# Load_Cape.net
KiCad netlist of a schematic drawn in EAGLE
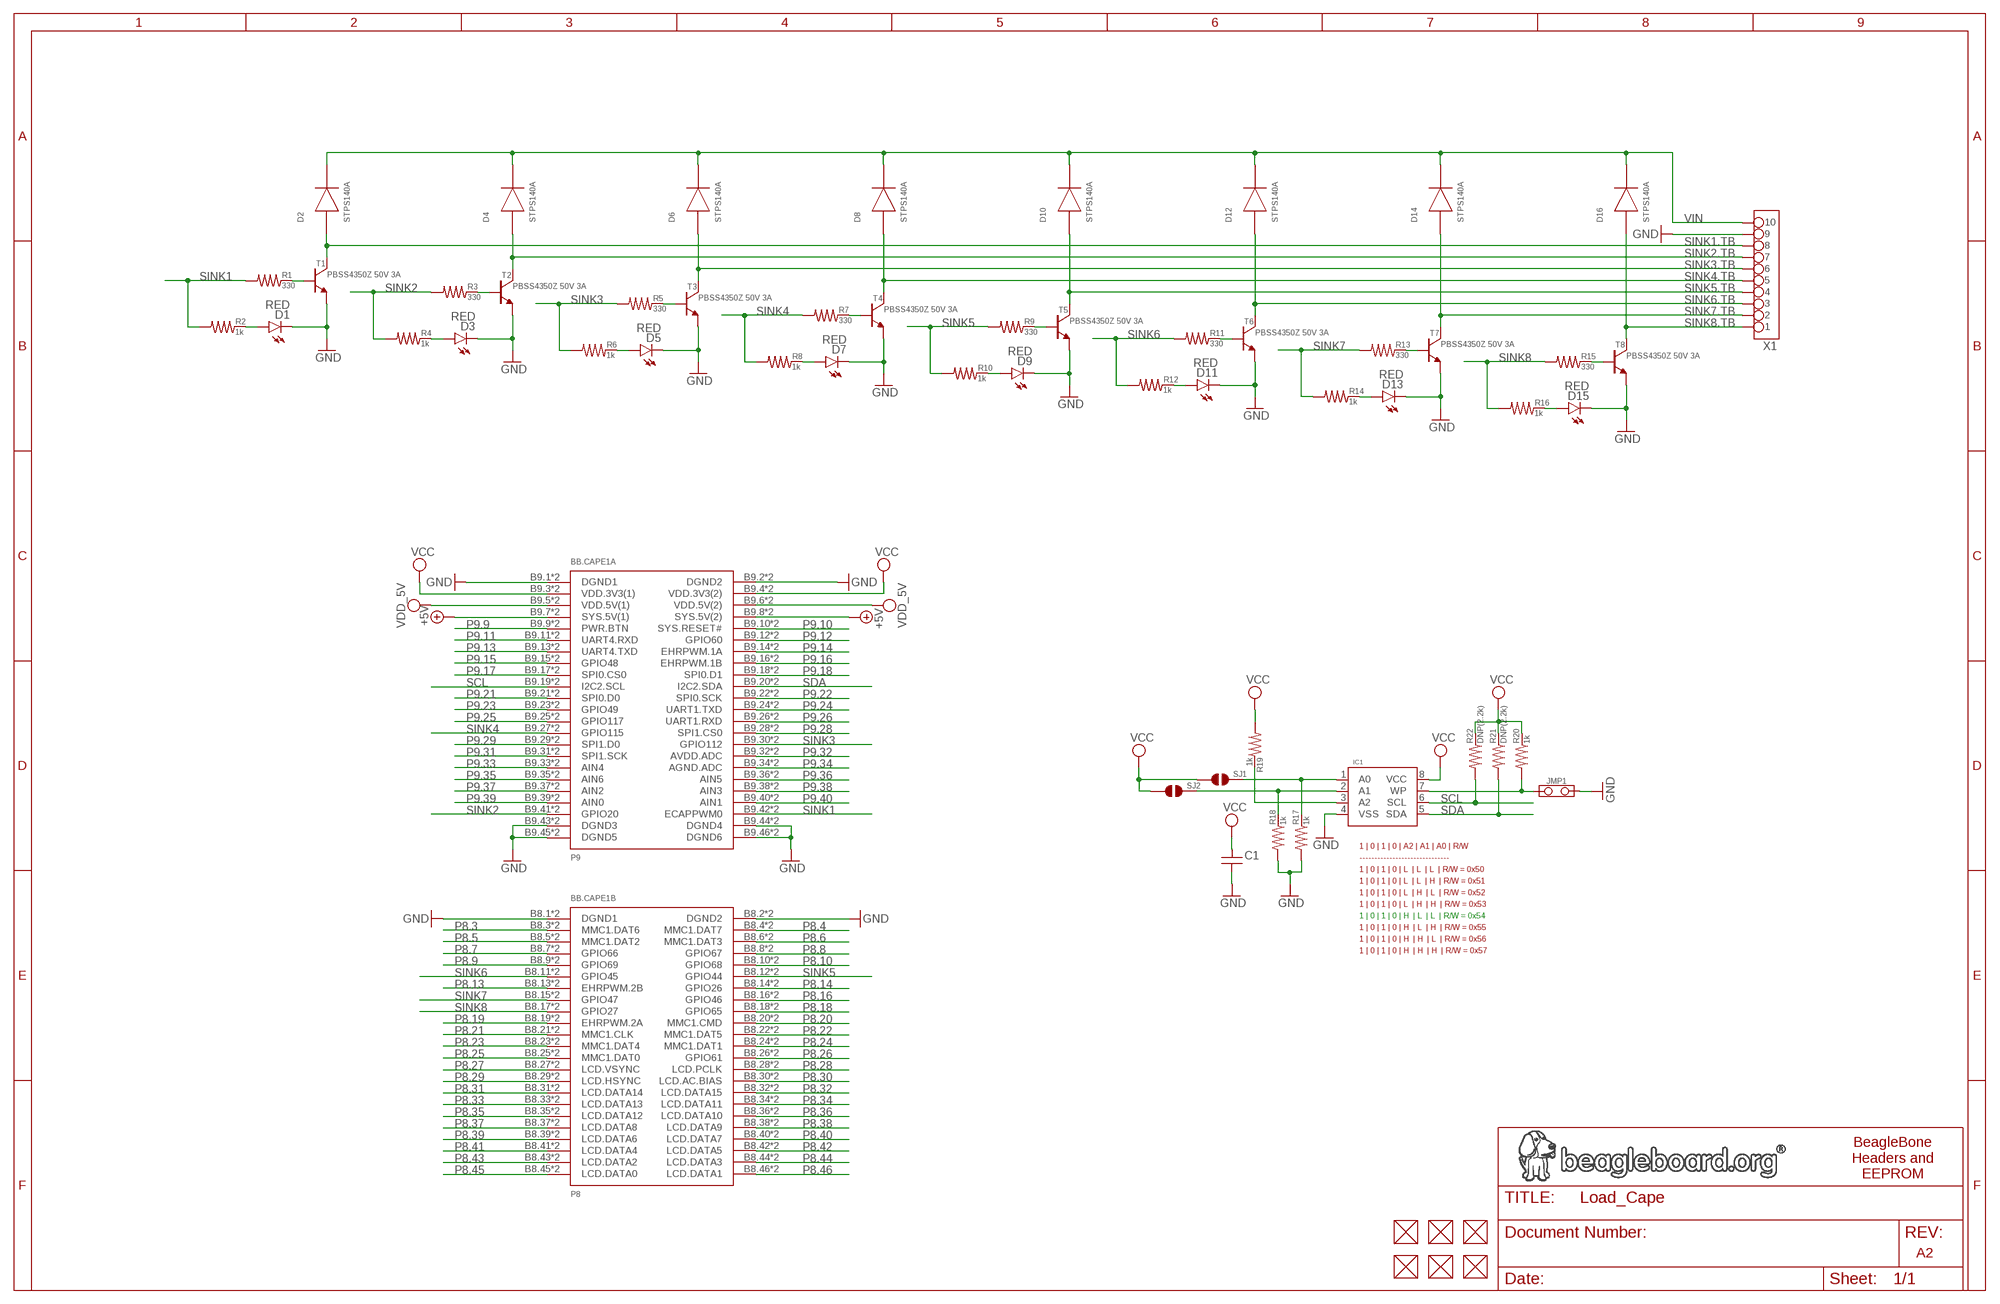
[diagram p0: schematic, sheet 1]

(export (version "E")
  (design (tool "Eeschema 10.0.6"))
  (components
    (comp (ref "BB.CAPE1")
      (value "BEAGLEBONE.CAPE.TOP/BOTTOM-PADS")
      (footprint "eagle-import:BEAGLEBONE.CAPE.TOP_BOTTOM-PADS")
      (libsource (lib "eagle-import") (part "BEAGLEBONE.CAPE.TOP/BOTTOM-PADS"))
    )
    (comp (ref "C1")
      (value "CAPACITOR-(INCH)-0402")
      (footprint "eagle-import:0402")
      (libsource (lib "eagle-import") (part "CAPACITOR-(INCH)-0402"))
    )
    (comp (ref "D1")
      (value "RED")
      (footprint "eagle-import:0805-LED")
      (libsource (lib "eagle-import") (part "LED-(INCH)-0805"))
    )
    (comp (ref "D2")
      (value "STPS140A")
      (footprint "eagle-import:DIODE_SMA")
      (libsource (lib "eagle-import") (part "DIODE_SMA"))
    )
    (comp (ref "D3")
      (value "RED")
      (footprint "eagle-import:0805-LED")
      (libsource (lib "eagle-import") (part "LED-(INCH)-0805"))
    )
    (comp (ref "D4")
      (value "STPS140A")
      (footprint "eagle-import:DIODE_SMA")
      (libsource (lib "eagle-import") (part "DIODE_SMA"))
    )
    (comp (ref "D5")
      (value "RED")
      (footprint "eagle-import:0805-LED")
      (libsource (lib "eagle-import") (part "LED-(INCH)-0805"))
    )
    (comp (ref "D6")
      (value "STPS140A")
      (footprint "eagle-import:DIODE_SMA")
      (libsource (lib "eagle-import") (part "DIODE_SMA"))
    )
    (comp (ref "D7")
      (value "RED")
      (footprint "eagle-import:0805-LED")
      (libsource (lib "eagle-import") (part "LED-(INCH)-0805"))
    )
    (comp (ref "D8")
      (value "STPS140A")
      (footprint "eagle-import:DIODE_SMA")
      (libsource (lib "eagle-import") (part "DIODE_SMA"))
    )
    (comp (ref "D9")
      (value "RED")
      (footprint "eagle-import:0805-LED")
      (libsource (lib "eagle-import") (part "LED-(INCH)-0805"))
    )
    (comp (ref "D10")
      (value "STPS140A")
      (footprint "eagle-import:DIODE_SMA")
      (libsource (lib "eagle-import") (part "DIODE_SMA"))
    )
    (comp (ref "D11")
      (value "RED")
      (footprint "eagle-import:0805-LED")
      (libsource (lib "eagle-import") (part "LED-(INCH)-0805"))
    )
    (comp (ref "D12")
      (value "STPS140A")
      (footprint "eagle-import:DIODE_SMA")
      (libsource (lib "eagle-import") (part "DIODE_SMA"))
    )
    (comp (ref "D13")
      (value "RED")
      (footprint "eagle-import:0805-LED")
      (libsource (lib "eagle-import") (part "LED-(INCH)-0805"))
    )
    (comp (ref "D14")
      (value "STPS140A")
      (footprint "eagle-import:DIODE_SMA")
      (libsource (lib "eagle-import") (part "DIODE_SMA"))
    )
    (comp (ref "D15")
      (value "RED")
      (footprint "eagle-import:0805-LED")
      (libsource (lib "eagle-import") (part "LED-(INCH)-0805"))
    )
    (comp (ref "D16")
      (value "STPS140A")
      (footprint "eagle-import:DIODE_SMA")
      (libsource (lib "eagle-import") (part "DIODE_SMA"))
    )
    (comp (ref "FUD1")
      (value "FIDUCIAL")
      (footprint "eagle-import:FIDUCIAL_40MIL")
      (libsource (lib "eagle-import") (part "FIDUCIAL"))
    )
    (comp (ref "FUD2")
      (value "FIDUCIAL")
      (footprint "eagle-import:FIDUCIAL_40MIL")
      (libsource (lib "eagle-import") (part "FIDUCIAL"))
    )
    (comp (ref "FUD3")
      (value "FIDUCIAL")
      (footprint "eagle-import:FIDUCIAL_40MIL")
      (libsource (lib "eagle-import") (part "FIDUCIAL"))
    )
    (comp (ref "FUD4")
      (value "FIDUCIAL")
      (footprint "eagle-import:FIDUCIAL_40MIL")
      (libsource (lib "eagle-import") (part "FIDUCIAL"))
    )
    (comp (ref "FUD5")
      (value "FIDUCIAL")
      (footprint "eagle-import:FIDUCIAL_40MIL")
      (libsource (lib "eagle-import") (part "FIDUCIAL"))
    )
    (comp (ref "FUD6")
      (value "FIDUCIAL")
      (footprint "eagle-import:FIDUCIAL_40MIL")
      (libsource (lib "eagle-import") (part "FIDUCIAL"))
    )
    (comp (ref "IC1")
      (value "CAT24C32")
      (footprint "eagle-import:UDFN8,2X3(ON-SEMI)")
      (libsource (lib "eagle-import") (part "CAT24C32"))
    )
    (comp (ref "JMP1")
      (value "JUMPER-(X2)")
      (footprint "eagle-import:JUMPER-(X2)")
      (libsource (lib "eagle-import") (part "JUMPER-(X2)"))
    )
    (comp (ref "R1")
      (value "330")
      (footprint "eagle-import:0402")
      (libsource (lib "eagle-import") (part "RESISTOR-(INCH)-0402"))
    )
    (comp (ref "R2")
      (value "1k")
      (footprint "eagle-import:0402")
      (libsource (lib "eagle-import") (part "RESISTOR-(INCH)-0402"))
    )
    (comp (ref "R3")
      (value "330")
      (footprint "eagle-import:0402")
      (libsource (lib "eagle-import") (part "RESISTOR-(INCH)-0402"))
    )
    (comp (ref "R4")
      (value "1k")
      (footprint "eagle-import:0402")
      (libsource (lib "eagle-import") (part "RESISTOR-(INCH)-0402"))
    )
    (comp (ref "R5")
      (value "330")
      (footprint "eagle-import:0402")
      (libsource (lib "eagle-import") (part "RESISTOR-(INCH)-0402"))
    )
    (comp (ref "R6")
      (value "1k")
      (footprint "eagle-import:0402")
      (libsource (lib "eagle-import") (part "RESISTOR-(INCH)-0402"))
    )
    (comp (ref "R7")
      (value "330")
      (footprint "eagle-import:0402")
      (libsource (lib "eagle-import") (part "RESISTOR-(INCH)-0402"))
    )
    (comp (ref "R8")
      (value "1k")
      (footprint "eagle-import:0402")
      (libsource (lib "eagle-import") (part "RESISTOR-(INCH)-0402"))
    )
    (comp (ref "R9")
      (value "330")
      (footprint "eagle-import:0402")
      (libsource (lib "eagle-import") (part "RESISTOR-(INCH)-0402"))
    )
    (comp (ref "R10")
      (value "1k")
      (footprint "eagle-import:0402")
      (libsource (lib "eagle-import") (part "RESISTOR-(INCH)-0402"))
    )
    (comp (ref "R11")
      (value "330")
      (footprint "eagle-import:0402")
      (libsource (lib "eagle-import") (part "RESISTOR-(INCH)-0402"))
    )
    (comp (ref "R12")
      (value "1k")
      (footprint "eagle-import:0402")
      (libsource (lib "eagle-import") (part "RESISTOR-(INCH)-0402"))
    )
    (comp (ref "R13")
      (value "330")
      (footprint "eagle-import:0402")
      (libsource (lib "eagle-import") (part "RESISTOR-(INCH)-0402"))
    )
    (comp (ref "R14")
      (value "1k")
      (footprint "eagle-import:0402")
      (libsource (lib "eagle-import") (part "RESISTOR-(INCH)-0402"))
    )
    (comp (ref "R15")
      (value "330")
      (footprint "eagle-import:0402")
      (libsource (lib "eagle-import") (part "RESISTOR-(INCH)-0402"))
    )
    (comp (ref "R16")
      (value "1k")
      (footprint "eagle-import:0402")
      (libsource (lib "eagle-import") (part "RESISTOR-(INCH)-0402"))
    )
    (comp (ref "R17")
      (value "1k")
      (footprint "eagle-import:0402")
      (libsource (lib "eagle-import") (part "RESISTOR-(INCH)-0402"))
    )
    (comp (ref "R18")
      (value "1k")
      (footprint "eagle-import:0402")
      (libsource (lib "eagle-import") (part "RESISTOR-(INCH)-0402"))
    )
    (comp (ref "R19")
      (value "1k")
      (footprint "eagle-import:0402")
      (libsource (lib "eagle-import") (part "RESISTOR-(INCH)-0402"))
    )
    (comp (ref "R20")
      (value "1k")
      (footprint "eagle-import:0402")
      (libsource (lib "eagle-import") (part "RESISTOR-(INCH)-0402"))
    )
    (comp (ref "R21")
      (value "DNP(2.2k)")
      (footprint "eagle-import:0402")
      (libsource (lib "eagle-import") (part "RESISTOR-(INCH)-0402"))
    )
    (comp (ref "R22")
      (value "DNP(2.2k)")
      (footprint "eagle-import:0402")
      (libsource (lib "eagle-import") (part "RESISTOR-(INCH)-0402"))
    )
    (comp (ref "SJ1")
      (value "SOLDER.JOINT-(INCH)-0402")
      (footprint "eagle-import:SOLDER.JOINT(0402)")
      (libsource (lib "eagle-import") (part "SOLDER.JOINT-(INCH)-0402"))
    )
    (comp (ref "SJ2")
      (value "SOLDER.JOINT-(INCH)-0402")
      (footprint "eagle-import:SOLDER.JOINT(0402)")
      (libsource (lib "eagle-import") (part "SOLDER.JOINT-(INCH)-0402"))
    )
    (comp (ref "T1")
      (value "PBSS4350Z 50V 3A")
      (footprint "eagle-import:SOT223")
      (libsource (lib "eagle-import") (part "PBSS4350Z"))
    )
    (comp (ref "T2")
      (value "PBSS4350Z 50V 3A")
      (footprint "eagle-import:SOT223")
      (libsource (lib "eagle-import") (part "PBSS4350Z"))
    )
    (comp (ref "T3")
      (value "PBSS4350Z 50V 3A")
      (footprint "eagle-import:SOT223")
      (libsource (lib "eagle-import") (part "PBSS4350Z"))
    )
    (comp (ref "T4")
      (value "PBSS4350Z 50V 3A")
      (footprint "eagle-import:SOT223")
      (libsource (lib "eagle-import") (part "PBSS4350Z"))
    )
    (comp (ref "T5")
      (value "PBSS4350Z 50V 3A")
      (footprint "eagle-import:SOT223")
      (libsource (lib "eagle-import") (part "PBSS4350Z"))
    )
    (comp (ref "T6")
      (value "PBSS4350Z 50V 3A")
      (footprint "eagle-import:SOT223")
      (libsource (lib "eagle-import") (part "PBSS4350Z"))
    )
    (comp (ref "T7")
      (value "PBSS4350Z 50V 3A")
      (footprint "eagle-import:SOT223")
      (libsource (lib "eagle-import") (part "PBSS4350Z"))
    )
    (comp (ref "T8")
      (value "PBSS4350Z 50V 3A")
      (footprint "eagle-import:SOT223")
      (libsource (lib "eagle-import") (part "PBSS4350Z"))
    )
    (comp (ref "X1")
      (value "TB-10TERM-150MIL.PITCH")
      (footprint "eagle-import:TERMINAL.BLOCK-10TERM-150MIL.PITCH")
      (libsource (lib "eagle-import") (part "TB-10TERM-150MIL.PITCH"))
    )
  )
  (nets
    (net (code "1") (name "+5V") (class "Default")
      (node (ref "BB.CAPE1") (pin "B9.7") (pinfunction "SYS.5V(1)_B9.7") (pintype "bidirectional"))
      (node (ref "BB.CAPE1") (pin "B9.8") (pinfunction "SYS.5V(2)_B9.8") (pintype "bidirectional"))
      (node (ref "BB.CAPE1") (pin "T9.7") (pinfunction "SYS.5V(1)_T9.7") (pintype "bidirectional"))
      (node (ref "BB.CAPE1") (pin "T9.8") (pinfunction "SYS.5V(2)_T9.8") (pintype "bidirectional"))
    )
    (net (code "2") (name "/P8.3") (class "Default")
      (node (ref "BB.CAPE1") (pin "B8.3") (pinfunction "MMC1.DAT6_B8.3") (pintype "bidirectional"))
      (node (ref "BB.CAPE1") (pin "T8.3") (pinfunction "MMC1.DAT6_T8.3") (pintype "bidirectional"))
    )
    (net (code "3") (name "/P8.4") (class "Default")
      (node (ref "BB.CAPE1") (pin "B8.4") (pinfunction "MMC1.DAT7_B8.4") (pintype "bidirectional"))
      (node (ref "BB.CAPE1") (pin "T8.4") (pinfunction "MMC1.DAT7_T8.4") (pintype "bidirectional"))
    )
    (net (code "4") (name "/P8.5") (class "Default")
      (node (ref "BB.CAPE1") (pin "B8.5") (pinfunction "MMC1.DAT2_B8.5") (pintype "bidirectional"))
      (node (ref "BB.CAPE1") (pin "T8.5") (pinfunction "MMC1.DAT2_T8.5") (pintype "bidirectional"))
    )
    (net (code "5") (name "/P8.6") (class "Default")
      (node (ref "BB.CAPE1") (pin "B8.6") (pinfunction "MMC1.DAT3_B8.6") (pintype "bidirectional"))
      (node (ref "BB.CAPE1") (pin "T8.6") (pinfunction "MMC1.DAT3_T8.6") (pintype "bidirectional"))
    )
    (net (code "6") (name "/P8.7") (class "Default")
      (node (ref "BB.CAPE1") (pin "B8.7") (pinfunction "GPIO66_B8.7") (pintype "bidirectional"))
      (node (ref "BB.CAPE1") (pin "T8.7") (pinfunction "GPIO66_T8.7") (pintype "bidirectional"))
    )
    (net (code "7") (name "/P8.8") (class "Default")
      (node (ref "BB.CAPE1") (pin "B8.8") (pinfunction "GPIO67_B8.8") (pintype "bidirectional"))
      (node (ref "BB.CAPE1") (pin "T8.8") (pinfunction "GPIO67_T8.8") (pintype "bidirectional"))
    )
    (net (code "8") (name "/P8.9") (class "Default")
      (node (ref "BB.CAPE1") (pin "B8.9") (pinfunction "GPIO69_B8.9") (pintype "bidirectional"))
      (node (ref "BB.CAPE1") (pin "T8.9") (pinfunction "GPIO69_T8.9") (pintype "bidirectional"))
    )
    (net (code "9") (name "/P8.10") (class "Default")
      (node (ref "BB.CAPE1") (pin "B8.10") (pinfunction "GPIO68_B8.10") (pintype "bidirectional"))
      (node (ref "BB.CAPE1") (pin "T8.10") (pinfunction "GPIO68_T8.10") (pintype "bidirectional"))
    )
    (net (code "10") (name "/P8.13") (class "Default")
      (node (ref "BB.CAPE1") (pin "B8.13") (pinfunction "EHRPWM.2B_B8.13") (pintype "bidirectional"))
      (node (ref "BB.CAPE1") (pin "T8.13") (pinfunction "EHRPWM.2B_T8.13") (pintype "bidirectional"))
    )
    (net (code "11") (name "/P8.14") (class "Default")
      (node (ref "BB.CAPE1") (pin "B8.14") (pinfunction "GPIO26_B8.14") (pintype "bidirectional"))
      (node (ref "BB.CAPE1") (pin "T8.14") (pinfunction "GPIO26_T8.14") (pintype "bidirectional"))
    )
    (net (code "12") (name "/P8.16") (class "Default")
      (node (ref "BB.CAPE1") (pin "B8.16") (pinfunction "GPIO46_B8.16") (pintype "bidirectional"))
      (node (ref "BB.CAPE1") (pin "T8.16") (pinfunction "GPIO46_T8.16") (pintype "bidirectional"))
    )
    (net (code "13") (name "/P8.18") (class "Default")
      (node (ref "BB.CAPE1") (pin "B8.18") (pinfunction "GPIO65_B8.18") (pintype "bidirectional"))
      (node (ref "BB.CAPE1") (pin "T8.18") (pinfunction "GPIO65_T8.18") (pintype "bidirectional"))
    )
    (net (code "14") (name "/P8.19") (class "Default")
      (node (ref "BB.CAPE1") (pin "B8.19") (pinfunction "EHRPWM.2A_B8.19") (pintype "bidirectional"))
      (node (ref "BB.CAPE1") (pin "T8.19") (pinfunction "EHRPWM.2A_T8.19") (pintype "bidirectional"))
    )
    (net (code "15") (name "/P8.20") (class "Default")
      (node (ref "BB.CAPE1") (pin "B8.20") (pinfunction "MMC1.CMD_B8.20") (pintype "bidirectional"))
      (node (ref "BB.CAPE1") (pin "T8.20") (pinfunction "MMC1.CMD_T8.20") (pintype "bidirectional"))
    )
    (net (code "16") (name "/P8.21") (class "Default")
      (node (ref "BB.CAPE1") (pin "B8.21") (pinfunction "MMC1.CLK_B8.21") (pintype "bidirectional"))
      (node (ref "BB.CAPE1") (pin "T8.21") (pinfunction "MMC1.CLK_T8.21") (pintype "bidirectional"))
    )
    (net (code "17") (name "/P8.22") (class "Default")
      (node (ref "BB.CAPE1") (pin "B8.22") (pinfunction "MMC1.DAT5_B8.22") (pintype "bidirectional"))
      (node (ref "BB.CAPE1") (pin "T8.22") (pinfunction "MMC1.DAT5_T8.22") (pintype "bidirectional"))
    )
    (net (code "18") (name "/P8.23") (class "Default")
      (node (ref "BB.CAPE1") (pin "B8.23") (pinfunction "MMC1.DAT4_B8.23") (pintype "bidirectional"))
      (node (ref "BB.CAPE1") (pin "T8.23") (pinfunction "MMC1.DAT4_T8.23") (pintype "bidirectional"))
    )
    (net (code "19") (name "/P8.24") (class "Default")
      (node (ref "BB.CAPE1") (pin "B8.24") (pinfunction "MMC1.DAT1_B8.24") (pintype "bidirectional"))
      (node (ref "BB.CAPE1") (pin "T8.24") (pinfunction "MMC1.DAT1_T8.24") (pintype "bidirectional"))
    )
    (net (code "20") (name "/P8.25") (class "Default")
      (node (ref "BB.CAPE1") (pin "B8.25") (pinfunction "MMC1.DAT0_B8.25") (pintype "bidirectional"))
      (node (ref "BB.CAPE1") (pin "T8.25") (pinfunction "MMC1.DAT0_T8.25") (pintype "bidirectional"))
    )
    (net (code "21") (name "/P8.26") (class "Default")
      (node (ref "BB.CAPE1") (pin "B8.26") (pinfunction "GPIO61_B8.26") (pintype "bidirectional"))
      (node (ref "BB.CAPE1") (pin "T8.26") (pinfunction "GPIO61_T8.26") (pintype "bidirectional"))
    )
    (net (code "22") (name "/P8.27") (class "Default")
      (node (ref "BB.CAPE1") (pin "B8.27") (pinfunction "LCD.VSYNC_B8.27") (pintype "bidirectional"))
      (node (ref "BB.CAPE1") (pin "T8.27") (pinfunction "LCD.VSYNC_T8.27") (pintype "bidirectional"))
    )
    (net (code "23") (name "/P8.28") (class "Default")
      (node (ref "BB.CAPE1") (pin "B8.28") (pinfunction "LCD.PCLK_B8.28") (pintype "bidirectional"))
      (node (ref "BB.CAPE1") (pin "T8.28") (pinfunction "LCD.PCLK_T8.28") (pintype "bidirectional"))
    )
    (net (code "24") (name "/P8.29") (class "Default")
      (node (ref "BB.CAPE1") (pin "B8.29") (pinfunction "LCD.HSYNC_B8.29") (pintype "bidirectional"))
      (node (ref "BB.CAPE1") (pin "T8.29") (pinfunction "LCD.HSYNC_T8.29") (pintype "bidirectional"))
    )
    (net (code "25") (name "/P8.30") (class "Default")
      (node (ref "BB.CAPE1") (pin "B8.30") (pinfunction "LCD.AC.BIAS_B8.30") (pintype "bidirectional"))
      (node (ref "BB.CAPE1") (pin "T8.30") (pinfunction "LCD.AC.BIAS_T8.30") (pintype "bidirectional"))
    )
    (net (code "26") (name "/P8.31") (class "Default")
      (node (ref "BB.CAPE1") (pin "B8.31") (pinfunction "LCD.DATA14_B8.31") (pintype "bidirectional"))
      (node (ref "BB.CAPE1") (pin "T8.31") (pinfunction "LCD.DATA14_T8.31") (pintype "bidirectional"))
    )
    (net (code "27") (name "/P8.32") (class "Default")
      (node (ref "BB.CAPE1") (pin "B8.32") (pinfunction "LCD.DATA15_B8.32") (pintype "bidirectional"))
      (node (ref "BB.CAPE1") (pin "T8.32") (pinfunction "LCD.DATA15_T8.32") (pintype "bidirectional"))
    )
    (net (code "28") (name "/P8.33") (class "Default")
      (node (ref "BB.CAPE1") (pin "B8.33") (pinfunction "LCD.DATA13_B8.33") (pintype "bidirectional"))
      (node (ref "BB.CAPE1") (pin "T8.33") (pinfunction "LCD.DATA13_T8.33") (pintype "bidirectional"))
    )
    (net (code "29") (name "/P8.34") (class "Default")
      (node (ref "BB.CAPE1") (pin "B8.34") (pinfunction "LCD.DATA11_B8.34") (pintype "bidirectional"))
      (node (ref "BB.CAPE1") (pin "T8.34") (pinfunction "LCD.DATA11_T8.34") (pintype "bidirectional"))
    )
    (net (code "30") (name "/P8.35") (class "Default")
      (node (ref "BB.CAPE1") (pin "B8.35") (pinfunction "LCD.DATA12_B8.35") (pintype "bidirectional"))
      (node (ref "BB.CAPE1") (pin "T8.35") (pinfunction "LCD.DATA12_T8.35") (pintype "bidirectional"))
    )
    (net (code "31") (name "/P8.36") (class "Default")
      (node (ref "BB.CAPE1") (pin "B8.36") (pinfunction "LCD.DATA10_B8.36") (pintype "bidirectional"))
      (node (ref "BB.CAPE1") (pin "T8.36") (pinfunction "LCD.DATA10_T8.36") (pintype "bidirectional"))
    )
    (net (code "32") (name "/P8.37") (class "Default")
      (node (ref "BB.CAPE1") (pin "B8.37") (pinfunction "LCD.DATA8_B8.37") (pintype "bidirectional"))
      (node (ref "BB.CAPE1") (pin "T8.37") (pinfunction "LCD.DATA8_T8.37") (pintype "bidirectional"))
    )
    (net (code "33") (name "/P8.38") (class "Default")
      (node (ref "BB.CAPE1") (pin "B8.38") (pinfunction "LCD.DATA9_B8.38") (pintype "bidirectional"))
      (node (ref "BB.CAPE1") (pin "T8.38") (pinfunction "LCD.DATA9_T8.38") (pintype "bidirectional"))
    )
    (net (code "34") (name "/P8.39") (class "Default")
      (node (ref "BB.CAPE1") (pin "B8.39") (pinfunction "LCD.DATA6_B8.39") (pintype "bidirectional"))
      (node (ref "BB.CAPE1") (pin "T8.39") (pinfunction "LCD.DATA6_T8.39") (pintype "bidirectional"))
    )
    (net (code "35") (name "/P8.40") (class "Default")
      (node (ref "BB.CAPE1") (pin "B8.40") (pinfunction "LCD.DATA7_B8.40") (pintype "bidirectional"))
      (node (ref "BB.CAPE1") (pin "T8.40") (pinfunction "LCD.DATA7_T8.40") (pintype "bidirectional"))
    )
    (net (code "36") (name "/P8.41") (class "Default")
      (node (ref "BB.CAPE1") (pin "B8.41") (pinfunction "LCD.DATA4_B8.41") (pintype "bidirectional"))
      (node (ref "BB.CAPE1") (pin "T8.41") (pinfunction "LCD.DATA4_T8.41") (pintype "bidirectional"))
    )
    (net (code "37") (name "/P8.42") (class "Default")
      (node (ref "BB.CAPE1") (pin "B8.42") (pinfunction "LCD.DATA5_B8.42") (pintype "bidirectional"))
      (node (ref "BB.CAPE1") (pin "T8.42") (pinfunction "LCD.DATA5_T8.42") (pintype "bidirectional"))
    )
    (net (code "38") (name "/P8.43") (class "Default")
      (node (ref "BB.CAPE1") (pin "B8.43") (pinfunction "LCD.DATA2_B8.43") (pintype "bidirectional"))
      (node (ref "BB.CAPE1") (pin "T8.43") (pinfunction "LCD.DATA2_T8.43") (pintype "bidirectional"))
    )
    (net (code "39") (name "/P8.44") (class "Default")
      (node (ref "BB.CAPE1") (pin "B8.44") (pinfunction "LCD.DATA3_B8.44") (pintype "bidirectional"))
      (node (ref "BB.CAPE1") (pin "T8.44") (pinfunction "LCD.DATA3_T8.44") (pintype "bidirectional"))
    )
    (net (code "40") (name "/P8.45") (class "Default")
      (node (ref "BB.CAPE1") (pin "B8.45") (pinfunction "LCD.DATA0_B8.45") (pintype "bidirectional"))
      (node (ref "BB.CAPE1") (pin "T8.45") (pinfunction "LCD.DATA0_T8.45") (pintype "bidirectional"))
    )
    (net (code "41") (name "/P8.46") (class "Default")
      (node (ref "BB.CAPE1") (pin "B8.46") (pinfunction "LCD.DATA1_B8.46") (pintype "bidirectional"))
      (node (ref "BB.CAPE1") (pin "T8.46") (pinfunction "LCD.DATA1_T8.46") (pintype "bidirectional"))
    )
    (net (code "42") (name "/P9.9") (class "Default")
      (node (ref "BB.CAPE1") (pin "B9.9") (pinfunction "PWR.BTN_B9.9") (pintype "bidirectional"))
      (node (ref "BB.CAPE1") (pin "T9.9") (pinfunction "PWR.BTN_T9.9") (pintype "bidirectional"))
    )
    (net (code "43") (name "/P9.10") (class "Default")
      (node (ref "BB.CAPE1") (pin "B9.10") (pinfunction "SYS.RESET#_B9.10") (pintype "bidirectional"))
      (node (ref "BB.CAPE1") (pin "T9.10") (pinfunction "SYS.RESET#_T9.10") (pintype "bidirectional"))
    )
    (net (code "44") (name "/P9.11") (class "Default")
      (node (ref "BB.CAPE1") (pin "B9.11") (pinfunction "UART4.RXD_B9.11") (pintype "bidirectional"))
      (node (ref "BB.CAPE1") (pin "T9.11") (pinfunction "UART4.RXD_T9.11") (pintype "bidirectional"))
    )
    (net (code "45") (name "/P9.12") (class "Default")
      (node (ref "BB.CAPE1") (pin "B9.12") (pinfunction "GPIO60_B9.12") (pintype "bidirectional"))
      (node (ref "BB.CAPE1") (pin "T9.12") (pinfunction "GPIO60_T9.12") (pintype "bidirectional"))
    )
    (net (code "46") (name "/P9.13") (class "Default")
      (node (ref "BB.CAPE1") (pin "B9.13") (pinfunction "UART4.TXD_B9.13") (pintype "bidirectional"))
      (node (ref "BB.CAPE1") (pin "T9.13") (pinfunction "UART4.TXD_T9.13") (pintype "bidirectional"))
    )
    (net (code "47") (name "/P9.14") (class "Default")
      (node (ref "BB.CAPE1") (pin "B9.14") (pinfunction "EHRPWM.1A_B9.14") (pintype "bidirectional"))
      (node (ref "BB.CAPE1") (pin "T9.14") (pinfunction "EHRPWM.1A_T9.14") (pintype "bidirectional"))
    )
    (net (code "48") (name "/P9.15") (class "Default")
      (node (ref "BB.CAPE1") (pin "B9.15") (pinfunction "GPIO48_B9.15") (pintype "bidirectional"))
      (node (ref "BB.CAPE1") (pin "T9.15") (pinfunction "GPIO48_T9.15") (pintype "bidirectional"))
    )
    (net (code "49") (name "/P9.16") (class "Default")
      (node (ref "BB.CAPE1") (pin "B9.16") (pinfunction "EHRPWM.1B_B9.16") (pintype "bidirectional"))
      (node (ref "BB.CAPE1") (pin "T9.16") (pinfunction "EHRPWM.1B_T9.16") (pintype "bidirectional"))
    )
    (net (code "50") (name "/P9.17") (class "Default")
      (node (ref "BB.CAPE1") (pin "B9.17") (pinfunction "SPI0.CS0_B9.17") (pintype "bidirectional"))
      (node (ref "BB.CAPE1") (pin "T9.17") (pinfunction "SPI0.CS0_T9.17") (pintype "bidirectional"))
    )
    (net (code "51") (name "/P9.18") (class "Default")
      (node (ref "BB.CAPE1") (pin "B9.18") (pinfunction "SPI0.D1_B9.18") (pintype "bidirectional"))
      (node (ref "BB.CAPE1") (pin "T9.18") (pinfunction "SPI0.D1_T9.18") (pintype "bidirectional"))
    )
    (net (code "52") (name "/P9.21") (class "Default")
      (node (ref "BB.CAPE1") (pin "B9.21") (pinfunction "SPI0.D0_B9.21") (pintype "bidirectional"))
      (node (ref "BB.CAPE1") (pin "T9.21") (pinfunction "SPI0.D0_T9.21") (pintype "bidirectional"))
    )
    (net (code "53") (name "/P9.22") (class "Default")
      (node (ref "BB.CAPE1") (pin "B9.22") (pinfunction "SPI0.SCK_B9.22") (pintype "bidirectional"))
      (node (ref "BB.CAPE1") (pin "T9.22") (pinfunction "SPI0.SCK_T9.22") (pintype "bidirectional"))
    )
    (net (code "54") (name "/P9.23") (class "Default")
      (node (ref "BB.CAPE1") (pin "B9.23") (pinfunction "GPIO49_B9.23") (pintype "bidirectional"))
      (node (ref "BB.CAPE1") (pin "T9.23") (pinfunction "GPIO49_T9.23") (pintype "bidirectional"))
    )
    (net (code "55") (name "/P9.24") (class "Default")
      (node (ref "BB.CAPE1") (pin "B9.24") (pinfunction "UART1.TXD_B9.24") (pintype "bidirectional"))
      (node (ref "BB.CAPE1") (pin "T9.24") (pinfunction "UART1.TXD_T9.24") (pintype "bidirectional"))
    )
    (net (code "56") (name "/P9.25") (class "Default")
      (node (ref "BB.CAPE1") (pin "B9.25") (pinfunction "GPIO117_B9.25") (pintype "bidirectional"))
      (node (ref "BB.CAPE1") (pin "T9.25") (pinfunction "GPIO117_T9.25") (pintype "bidirectional"))
    )
    (net (code "57") (name "/P9.26") (class "Default")
      (node (ref "BB.CAPE1") (pin "B9.26") (pinfunction "UART1.RXD_B9.26") (pintype "bidirectional"))
      (node (ref "BB.CAPE1") (pin "T9.26") (pinfunction "UART1.RXD_T9.26") (pintype "bidirectional"))
    )
    (net (code "58") (name "/P9.28") (class "Default")
      (node (ref "BB.CAPE1") (pin "B9.28") (pinfunction "SPI1.CS0_B9.28") (pintype "bidirectional"))
      (node (ref "BB.CAPE1") (pin "T9.28") (pinfunction "SPI1.CS0_T9.28") (pintype "bidirectional"))
    )
    (net (code "59") (name "/P9.29") (class "Default")
      (node (ref "BB.CAPE1") (pin "B9.29") (pinfunction "SPI1.D0_B9.29") (pintype "bidirectional"))
      (node (ref "BB.CAPE1") (pin "T9.29") (pinfunction "SPI1.D0_T9.29") (pintype "bidirectional"))
    )
    (net (code "60") (name "/P9.31") (class "Default")
      (node (ref "BB.CAPE1") (pin "B9.31") (pinfunction "SPI1.SCK_B9.31") (pintype "bidirectional"))
      (node (ref "BB.CAPE1") (pin "T9.31") (pinfunction "SPI1.SCK_T9.31") (pintype "bidirectional"))
    )
    (net (code "61") (name "/P9.32") (class "Default")
      (node (ref "BB.CAPE1") (pin "B9.32") (pinfunction "AVDD.ADC_B9.32") (pintype "bidirectional"))
      (node (ref "BB.CAPE1") (pin "T9.32") (pinfunction "AVDD.ADC_T9.32") (pintype "bidirectional"))
    )
    (net (code "62") (name "/P9.33") (class "Default")
      (node (ref "BB.CAPE1") (pin "B9.33") (pinfunction "AIN4_B9.33") (pintype "bidirectional"))
      (node (ref "BB.CAPE1") (pin "T9.33") (pinfunction "AIN4_T9.33") (pintype "bidirectional"))
    )
    (net (code "63") (name "/P9.34") (class "Default")
      (node (ref "BB.CAPE1") (pin "B9.34") (pinfunction "AGND.ADC_B9.34") (pintype "bidirectional"))
      (node (ref "BB.CAPE1") (pin "T9.34") (pinfunction "AGND.ADC_T9.34") (pintype "bidirectional"))
    )
    (net (code "64") (name "/P9.35") (class "Default")
      (node (ref "BB.CAPE1") (pin "B9.35") (pinfunction "AIN6_B9.35") (pintype "bidirectional"))
      (node (ref "BB.CAPE1") (pin "T9.35") (pinfunction "AIN6_T9.35") (pintype "bidirectional"))
    )
    (net (code "65") (name "/P9.36") (class "Default")
      (node (ref "BB.CAPE1") (pin "B9.36") (pinfunction "AIN5_B9.36") (pintype "bidirectional"))
      (node (ref "BB.CAPE1") (pin "T9.36") (pinfunction "AIN5_T9.36") (pintype "bidirectional"))
    )
    (net (code "66") (name "/P9.37") (class "Default")
      (node (ref "BB.CAPE1") (pin "B9.37") (pinfunction "AIN2_B9.37") (pintype "bidirectional"))
      (node (ref "BB.CAPE1") (pin "T9.37") (pinfunction "AIN2_T9.37") (pintype "bidirectional"))
    )
    (net (code "67") (name "/P9.38") (class "Default")
      (node (ref "BB.CAPE1") (pin "B9.38") (pinfunction "AIN3_B9.38") (pintype "bidirectional"))
      (node (ref "BB.CAPE1") (pin "T9.38") (pinfunction "AIN3_T9.38") (pintype "bidirectional"))
    )
    (net (code "68") (name "/P9.39") (class "Default")
      (node (ref "BB.CAPE1") (pin "B9.39") (pinfunction "AIN0_B9.39") (pintype "bidirectional"))
      (node (ref "BB.CAPE1") (pin "T9.39") (pinfunction "AIN0_T9.39") (pintype "bidirectional"))
    )
    (net (code "69") (name "/P9.40") (class "Default")
      (node (ref "BB.CAPE1") (pin "B9.40") (pinfunction "AIN1_B9.40") (pintype "bidirectional"))
      (node (ref "BB.CAPE1") (pin "T9.40") (pinfunction "AIN1_T9.40") (pintype "bidirectional"))
    )
    (net (code "70") (name "/SCL") (class "Default")
      (node (ref "BB.CAPE1") (pin "B9.19") (pinfunction "I2C2.SCL_B9.19") (pintype "bidirectional"))
      (node (ref "BB.CAPE1") (pin "T9.19") (pinfunction "I2C2.SCL_T9.19") (pintype "bidirectional"))
      (node (ref "IC1") (pin "6") (pinfunction "SCL_6") (pintype "bidirectional"))
      (node (ref "R22") (pin "1") (pinfunction "1_1") (pintype "bidirectional"))
    )
    (net (code "71") (name "/SDA") (class "Default")
      (node (ref "BB.CAPE1") (pin "B9.20") (pinfunction "I2C2.SDA_B9.20") (pintype "bidirectional"))
      (node (ref "BB.CAPE1") (pin "T9.20") (pinfunction "I2C2.SDA_T9.20") (pintype "bidirectional"))
      (node (ref "IC1") (pin "5") (pinfunction "SDA_5") (pintype "bidirectional"))
      (node (ref "R21") (pin "1") (pinfunction "1_1") (pintype "bidirectional"))
    )
    (net (code "72") (name "/SINK1") (class "Default")
      (node (ref "BB.CAPE1") (pin "B9.42") (pinfunction "ECAPPWM0_B9.42") (pintype "bidirectional"))
      (node (ref "BB.CAPE1") (pin "T9.42") (pinfunction "ECAPPWM0_T9.42") (pintype "bidirectional"))
      (node (ref "R1") (pin "1") (pinfunction "1_1") (pintype "bidirectional"))
      (node (ref "R2") (pin "1") (pinfunction "1_1") (pintype "bidirectional"))
    )
    (net (code "73") (name "/SINK1.TB") (class "Default")
      (node (ref "D2") (pin "A") (pinfunction "A_A") (pintype "bidirectional"))
      (node (ref "T1") (pin "2") (pinfunction "C_2") (pintype "passive"))
      (node (ref "T1") (pin "4") (pinfunction "C_4") (pintype "passive"))
      (node (ref "X1") (pin "8") (pinfunction "8_8") (pintype "bidirectional"))
    )
    (net (code "74") (name "/SINK2") (class "Default")
      (node (ref "BB.CAPE1") (pin "B9.41") (pinfunction "GPIO20_B9.41") (pintype "bidirectional"))
      (node (ref "BB.CAPE1") (pin "T9.41") (pinfunction "GPIO20_T9.41") (pintype "bidirectional"))
      (node (ref "R3") (pin "1") (pinfunction "1_1") (pintype "bidirectional"))
      (node (ref "R4") (pin "1") (pinfunction "1_1") (pintype "bidirectional"))
    )
    (net (code "75") (name "/SINK2.TB") (class "Default")
      (node (ref "D4") (pin "A") (pinfunction "A_A") (pintype "bidirectional"))
      (node (ref "T2") (pin "2") (pinfunction "C_2") (pintype "passive"))
      (node (ref "T2") (pin "4") (pinfunction "C_4") (pintype "passive"))
      (node (ref "X1") (pin "7") (pinfunction "7_7") (pintype "bidirectional"))
    )
    (net (code "76") (name "/SINK3") (class "Default")
      (node (ref "BB.CAPE1") (pin "B9.30") (pinfunction "GPIO112_B9.30") (pintype "bidirectional"))
      (node (ref "BB.CAPE1") (pin "T9.30") (pinfunction "GPIO112_T9.30") (pintype "bidirectional"))
      (node (ref "R5") (pin "1") (pinfunction "1_1") (pintype "bidirectional"))
      (node (ref "R6") (pin "1") (pinfunction "1_1") (pintype "bidirectional"))
    )
    (net (code "77") (name "/SINK3.TB") (class "Default")
      (node (ref "D6") (pin "A") (pinfunction "A_A") (pintype "bidirectional"))
      (node (ref "T3") (pin "2") (pinfunction "C_2") (pintype "passive"))
      (node (ref "T3") (pin "4") (pinfunction "C_4") (pintype "passive"))
      (node (ref "X1") (pin "6") (pinfunction "6_6") (pintype "bidirectional"))
    )
    (net (code "78") (name "/SINK4") (class "Default")
      (node (ref "BB.CAPE1") (pin "B9.27") (pinfunction "GPIO115_B9.27") (pintype "bidirectional"))
      (node (ref "BB.CAPE1") (pin "T9.27") (pinfunction "GPIO115_T9.27") (pintype "bidirectional"))
      (node (ref "R7") (pin "1") (pinfunction "1_1") (pintype "bidirectional"))
      (node (ref "R8") (pin "1") (pinfunction "1_1") (pintype "bidirectional"))
    )
    (net (code "79") (name "/SINK4.TB") (class "Default")
      (node (ref "D8") (pin "A") (pinfunction "A_A") (pintype "bidirectional"))
      (node (ref "T4") (pin "2") (pinfunction "C_2") (pintype "passive"))
      (node (ref "T4") (pin "4") (pinfunction "C_4") (pintype "passive"))
      (node (ref "X1") (pin "5") (pinfunction "5_5") (pintype "bidirectional"))
    )
    (net (code "80") (name "/SINK5") (class "Default")
      (node (ref "BB.CAPE1") (pin "B8.12") (pinfunction "GPIO44_B8.12") (pintype "bidirectional"))
      (node (ref "BB.CAPE1") (pin "T8.12") (pinfunction "GPIO44_T8.12") (pintype "bidirectional"))
      (node (ref "R10") (pin "1") (pinfunction "1_1") (pintype "bidirectional"))
      (node (ref "R9") (pin "1") (pinfunction "1_1") (pintype "bidirectional"))
    )
    (net (code "81") (name "/SINK5.TB") (class "Default")
      (node (ref "D10") (pin "A") (pinfunction "A_A") (pintype "bidirectional"))
      (node (ref "T5") (pin "2") (pinfunction "C_2") (pintype "passive"))
      (node (ref "T5") (pin "4") (pinfunction "C_4") (pintype "passive"))
      (node (ref "X1") (pin "4") (pinfunction "4_4") (pintype "bidirectional"))
    )
    (net (code "82") (name "/SINK6") (class "Default")
      (node (ref "BB.CAPE1") (pin "B8.11") (pinfunction "GPIO45_B8.11") (pintype "bidirectional"))
      (node (ref "BB.CAPE1") (pin "T8.11") (pinfunction "GPIO45_T8.11") (pintype "bidirectional"))
      (node (ref "R11") (pin "1") (pinfunction "1_1") (pintype "bidirectional"))
      (node (ref "R12") (pin "1") (pinfunction "1_1") (pintype "bidirectional"))
    )
    (net (code "83") (name "/SINK6.TB") (class "Default")
      (node (ref "D12") (pin "A") (pinfunction "A_A") (pintype "bidirectional"))
      (node (ref "T6") (pin "2") (pinfunction "C_2") (pintype "passive"))
      (node (ref "T6") (pin "4") (pinfunction "C_4") (pintype "passive"))
      (node (ref "X1") (pin "3") (pinfunction "3_3") (pintype "bidirectional"))
    )
    (net (code "84") (name "/SINK7") (class "Default")
      (node (ref "BB.CAPE1") (pin "B8.15") (pinfunction "GPIO47_B8.15") (pintype "bidirectional"))
      (node (ref "BB.CAPE1") (pin "T8.15") (pinfunction "GPIO47_T8.15") (pintype "bidirectional"))
      (node (ref "R13") (pin "1") (pinfunction "1_1") (pintype "bidirectional"))
      (node (ref "R14") (pin "1") (pinfunction "1_1") (pintype "bidirectional"))
    )
    (net (code "85") (name "/SINK7.TB") (class "Default")
      (node (ref "D14") (pin "A") (pinfunction "A_A") (pintype "bidirectional"))
      (node (ref "T7") (pin "2") (pinfunction "C_2") (pintype "passive"))
      (node (ref "T7") (pin "4") (pinfunction "C_4") (pintype "passive"))
      (node (ref "X1") (pin "2") (pinfunction "2_2") (pintype "bidirectional"))
    )
    (net (code "86") (name "/SINK8") (class "Default")
      (node (ref "BB.CAPE1") (pin "B8.17") (pinfunction "GPIO27_B8.17") (pintype "bidirectional"))
      (node (ref "BB.CAPE1") (pin "T8.17") (pinfunction "GPIO27_T8.17") (pintype "bidirectional"))
      (node (ref "R15") (pin "1") (pinfunction "1_1") (pintype "bidirectional"))
      (node (ref "R16") (pin "1") (pinfunction "1_1") (pintype "bidirectional"))
    )
    (net (code "87") (name "/SINK8.TB") (class "Default")
      (node (ref "D16") (pin "A") (pinfunction "A_A") (pintype "bidirectional"))
      (node (ref "T8") (pin "2") (pinfunction "C_2") (pintype "passive"))
      (node (ref "T8") (pin "4") (pinfunction "C_4") (pintype "passive"))
      (node (ref "X1") (pin "1") (pinfunction "1_1") (pintype "bidirectional"))
    )
    (net (code "88") (name "/VIN") (class "Default")
      (node (ref "D10") (pin "K") (pinfunction "K_K") (pintype "bidirectional"))
      (node (ref "D12") (pin "K") (pinfunction "K_K") (pintype "bidirectional"))
      (node (ref "D14") (pin "K") (pinfunction "K_K") (pintype "bidirectional"))
      (node (ref "D16") (pin "K") (pinfunction "K_K") (pintype "bidirectional"))
      (node (ref "D2") (pin "K") (pinfunction "K_K") (pintype "bidirectional"))
      (node (ref "D4") (pin "K") (pinfunction "K_K") (pintype "bidirectional"))
      (node (ref "D6") (pin "K") (pinfunction "K_K") (pintype "bidirectional"))
      (node (ref "D8") (pin "K") (pinfunction "K_K") (pintype "bidirectional"))
      (node (ref "X1") (pin "10") (pinfunction "10_10") (pintype "bidirectional"))
    )
    (net (code "89") (name "GND") (class "Default")
      (node (ref "BB.CAPE1") (pin "B8.1") (pinfunction "DGND1_B8.1") (pintype "bidirectional"))
      (node (ref "BB.CAPE1") (pin "B8.2") (pinfunction "DGND2_B8.2") (pintype "bidirectional"))
      (node (ref "BB.CAPE1") (pin "B9.1") (pinfunction "DGND1_B9.1") (pintype "bidirectional"))
      (node (ref "BB.CAPE1") (pin "B9.2") (pinfunction "DGND2_B9.2") (pintype "bidirectional"))
      (node (ref "BB.CAPE1") (pin "B9.43") (pinfunction "DGND3_B9.43") (pintype "bidirectional"))
      (node (ref "BB.CAPE1") (pin "B9.44") (pinfunction "DGND4_B9.44") (pintype "bidirectional"))
      (node (ref "BB.CAPE1") (pin "B9.45") (pinfunction "DGND5_B9.45") (pintype "bidirectional"))
      (node (ref "BB.CAPE1") (pin "B9.46") (pinfunction "DGND6_B9.46") (pintype "bidirectional"))
      (node (ref "BB.CAPE1") (pin "T8.1") (pinfunction "DGND1_T8.1") (pintype "bidirectional"))
      (node (ref "BB.CAPE1") (pin "T8.2") (pinfunction "DGND2_T8.2") (pintype "bidirectional"))
      (node (ref "BB.CAPE1") (pin "T9.1") (pinfunction "DGND1_T9.1") (pintype "bidirectional"))
      (node (ref "BB.CAPE1") (pin "T9.2") (pinfunction "DGND2_T9.2") (pintype "bidirectional"))
      (node (ref "BB.CAPE1") (pin "T9.43") (pinfunction "DGND3_T9.43") (pintype "bidirectional"))
      (node (ref "BB.CAPE1") (pin "T9.44") (pinfunction "DGND4_T9.44") (pintype "bidirectional"))
      (node (ref "BB.CAPE1") (pin "T9.45") (pinfunction "DGND5_T9.45") (pintype "bidirectional"))
      (node (ref "BB.CAPE1") (pin "T9.46") (pinfunction "DGND6_T9.46") (pintype "bidirectional"))
      (node (ref "C1") (pin "2") (pinfunction "2_2") (pintype "bidirectional"))
      (node (ref "D1") (pin "K") (pinfunction "K_K") (pintype "passive"))
      (node (ref "D11") (pin "K") (pinfunction "K_K") (pintype "passive"))
      (node (ref "D13") (pin "K") (pinfunction "K_K") (pintype "passive"))
      (node (ref "D15") (pin "K") (pinfunction "K_K") (pintype "passive"))
      (node (ref "D3") (pin "K") (pinfunction "K_K") (pintype "passive"))
      (node (ref "D5") (pin "K") (pinfunction "K_K") (pintype "passive"))
      (node (ref "D7") (pin "K") (pinfunction "K_K") (pintype "passive"))
      (node (ref "D9") (pin "K") (pinfunction "K_K") (pintype "passive"))
      (node (ref "IC1") (pin "4") (pinfunction "VSS_4") (pintype "bidirectional"))
      (node (ref "JMP1") (pin "2") (pinfunction "2_2") (pintype "bidirectional"))
      (node (ref "R17") (pin "1") (pinfunction "1_1") (pintype "bidirectional"))
      (node (ref "R18") (pin "1") (pinfunction "1_1") (pintype "bidirectional"))
      (node (ref "T1") (pin "3") (pinfunction "E_3") (pintype "passive"))
      (node (ref "T2") (pin "3") (pinfunction "E_3") (pintype "passive"))
      (node (ref "T3") (pin "3") (pinfunction "E_3") (pintype "passive"))
      (node (ref "T4") (pin "3") (pinfunction "E_3") (pintype "passive"))
      (node (ref "T5") (pin "3") (pinfunction "E_3") (pintype "passive"))
      (node (ref "T6") (pin "3") (pinfunction "E_3") (pintype "passive"))
      (node (ref "T7") (pin "3") (pinfunction "E_3") (pintype "passive"))
      (node (ref "T8") (pin "3") (pinfunction "E_3") (pintype "passive"))
      (node (ref "X1") (pin "9") (pinfunction "9_9") (pintype "bidirectional"))
    )
    (net (code "90") (name "Net-(D1-PadA)") (class "Default")
      (node (ref "D1") (pin "A") (pinfunction "A_A") (pintype "passive"))
      (node (ref "R2") (pin "2") (pinfunction "2_2") (pintype "bidirectional"))
    )
    (net (code "91") (name "Net-(D3-PadA)") (class "Default")
      (node (ref "D3") (pin "A") (pinfunction "A_A") (pintype "passive"))
      (node (ref "R4") (pin "2") (pinfunction "2_2") (pintype "bidirectional"))
    )
    (net (code "92") (name "Net-(D5-PadA)") (class "Default")
      (node (ref "D5") (pin "A") (pinfunction "A_A") (pintype "passive"))
      (node (ref "R6") (pin "2") (pinfunction "2_2") (pintype "bidirectional"))
    )
    (net (code "93") (name "Net-(D7-PadA)") (class "Default")
      (node (ref "D7") (pin "A") (pinfunction "A_A") (pintype "passive"))
      (node (ref "R8") (pin "2") (pinfunction "2_2") (pintype "bidirectional"))
    )
    (net (code "94") (name "Net-(D9-PadA)") (class "Default")
      (node (ref "D9") (pin "A") (pinfunction "A_A") (pintype "passive"))
      (node (ref "R10") (pin "2") (pinfunction "2_2") (pintype "bidirectional"))
    )
    (net (code "95") (name "Net-(D11-PadA)") (class "Default")
      (node (ref "D11") (pin "A") (pinfunction "A_A") (pintype "passive"))
      (node (ref "R12") (pin "2") (pinfunction "2_2") (pintype "bidirectional"))
    )
    (net (code "96") (name "Net-(D13-PadA)") (class "Default")
      (node (ref "D13") (pin "A") (pinfunction "A_A") (pintype "passive"))
      (node (ref "R14") (pin "2") (pinfunction "2_2") (pintype "bidirectional"))
    )
    (net (code "97") (name "Net-(D15-PadA)") (class "Default")
      (node (ref "D15") (pin "A") (pinfunction "A_A") (pintype "passive"))
      (node (ref "R16") (pin "2") (pinfunction "2_2") (pintype "bidirectional"))
    )
    (net (code "98") (name "Net-(IC1-A0)") (class "Default")
      (node (ref "IC1") (pin "1") (pinfunction "A0_1") (pintype "bidirectional"))
      (node (ref "R17") (pin "2") (pinfunction "2_2") (pintype "bidirectional"))
      (node (ref "SJ1") (pin "2") (pinfunction "2_2") (pintype "bidirectional"))
    )
    (net (code "99") (name "Net-(IC1-A1)") (class "Default")
      (node (ref "IC1") (pin "2") (pinfunction "A1_2") (pintype "bidirectional"))
      (node (ref "R18") (pin "2") (pinfunction "2_2") (pintype "bidirectional"))
      (node (ref "SJ2") (pin "2") (pinfunction "2_2") (pintype "bidirectional"))
    )
    (net (code "100") (name "Net-(IC1-A2)") (class "Default")
      (node (ref "IC1") (pin "3") (pinfunction "A2_3") (pintype "bidirectional"))
      (node (ref "R19") (pin "2") (pinfunction "2_2") (pintype "bidirectional"))
    )
    (net (code "101") (name "Net-(IC1-WP)") (class "Default")
      (node (ref "IC1") (pin "7") (pinfunction "WP_7") (pintype "bidirectional"))
      (node (ref "JMP1") (pin "1") (pinfunction "1_1") (pintype "bidirectional"))
      (node (ref "R20") (pin "1") (pinfunction "1_1") (pintype "bidirectional"))
    )
    (net (code "102") (name "Net-(T1-B)") (class "Default")
      (node (ref "R1") (pin "2") (pinfunction "2_2") (pintype "bidirectional"))
      (node (ref "T1") (pin "1") (pinfunction "B_1") (pintype "passive"))
    )
    (net (code "103") (name "Net-(T2-B)") (class "Default")
      (node (ref "R3") (pin "2") (pinfunction "2_2") (pintype "bidirectional"))
      (node (ref "T2") (pin "1") (pinfunction "B_1") (pintype "passive"))
    )
    (net (code "104") (name "Net-(T3-B)") (class "Default")
      (node (ref "R5") (pin "2") (pinfunction "2_2") (pintype "bidirectional"))
      (node (ref "T3") (pin "1") (pinfunction "B_1") (pintype "passive"))
    )
    (net (code "105") (name "Net-(T4-B)") (class "Default")
      (node (ref "R7") (pin "2") (pinfunction "2_2") (pintype "bidirectional"))
      (node (ref "T4") (pin "1") (pinfunction "B_1") (pintype "passive"))
    )
    (net (code "106") (name "Net-(T5-B)") (class "Default")
      (node (ref "R9") (pin "2") (pinfunction "2_2") (pintype "bidirectional"))
      (node (ref "T5") (pin "1") (pinfunction "B_1") (pintype "passive"))
    )
    (net (code "107") (name "Net-(T6-B)") (class "Default")
      (node (ref "R11") (pin "2") (pinfunction "2_2") (pintype "bidirectional"))
      (node (ref "T6") (pin "1") (pinfunction "B_1") (pintype "passive"))
    )
    (net (code "108") (name "Net-(T7-B)") (class "Default")
      (node (ref "R13") (pin "2") (pinfunction "2_2") (pintype "bidirectional"))
      (node (ref "T7") (pin "1") (pinfunction "B_1") (pintype "passive"))
    )
    (net (code "109") (name "Net-(T8-B)") (class "Default")
      (node (ref "R15") (pin "2") (pinfunction "2_2") (pintype "bidirectional"))
      (node (ref "T8") (pin "1") (pinfunction "B_1") (pintype "passive"))
    )
    (net (code "110") (name "VCC") (class "Default")
      (node (ref "BB.CAPE1") (pin "B9.3") (pinfunction "VDD.3V3(1)_B9.3") (pintype "bidirectional"))
      (node (ref "BB.CAPE1") (pin "B9.4") (pinfunction "VDD.3V3(2)_B9.4") (pintype "bidirectional"))
      (node (ref "BB.CAPE1") (pin "T9.3") (pinfunction "VDD.3V3(1)_T9.3") (pintype "bidirectional"))
      (node (ref "BB.CAPE1") (pin "T9.4") (pinfunction "VDD.3V3(2)_T9.4") (pintype "bidirectional"))
      (node (ref "C1") (pin "1") (pinfunction "1_1") (pintype "bidirectional"))
      (node (ref "IC1") (pin "8") (pinfunction "VCC_8") (pintype "bidirectional"))
      (node (ref "R19") (pin "1") (pinfunction "1_1") (pintype "bidirectional"))
      (node (ref "R20") (pin "2") (pinfunction "2_2") (pintype "bidirectional"))
      (node (ref "R21") (pin "2") (pinfunction "2_2") (pintype "bidirectional"))
      (node (ref "R22") (pin "2") (pinfunction "2_2") (pintype "bidirectional"))
      (node (ref "SJ1") (pin "1") (pinfunction "1_1") (pintype "bidirectional"))
      (node (ref "SJ2") (pin "1") (pinfunction "1_1") (pintype "bidirectional"))
    )
    (net (code "111") (name "VDD_5V") (class "Default")
      (node (ref "BB.CAPE1") (pin "B9.5") (pinfunction "VDD.5V(1)_B9.5") (pintype "bidirectional"))
      (node (ref "BB.CAPE1") (pin "B9.6") (pinfunction "VDD.5V(2)_B9.6") (pintype "bidirectional"))
      (node (ref "BB.CAPE1") (pin "T9.5") (pinfunction "VDD.5V(1)_T9.5") (pintype "bidirectional"))
      (node (ref "BB.CAPE1") (pin "T9.6") (pinfunction "VDD.5V(2)_T9.6") (pintype "bidirectional"))
    )
    (net (code "112") (name "unconnected-(FUD1-PadP$1)") (class "Default")
      (node (ref "FUD1") (pin "P$1") (pinfunction "P$1_P$1") (pintype "no_connect"))
    )
    (net (code "113") (name "unconnected-(FUD2-PadP$1)") (class "Default")
      (node (ref "FUD2") (pin "P$1") (pinfunction "P$1_P$1") (pintype "no_connect"))
    )
    (net (code "114") (name "unconnected-(FUD3-PadP$1)") (class "Default")
      (node (ref "FUD3") (pin "P$1") (pinfunction "P$1_P$1") (pintype "no_connect"))
    )
    (net (code "115") (name "unconnected-(FUD4-PadP$1)") (class "Default")
      (node (ref "FUD4") (pin "P$1") (pinfunction "P$1_P$1") (pintype "no_connect"))
    )
    (net (code "116") (name "unconnected-(FUD5-PadP$1)") (class "Default")
      (node (ref "FUD5") (pin "P$1") (pinfunction "P$1_P$1") (pintype "no_connect"))
    )
    (net (code "117") (name "unconnected-(FUD6-PadP$1)") (class "Default")
      (node (ref "FUD6") (pin "P$1") (pinfunction "P$1_P$1") (pintype "no_connect"))
    )
  )
)
